# shield_I2C_latest_edit.net
KiCad netlist of a schematic drawn in Altium Designer
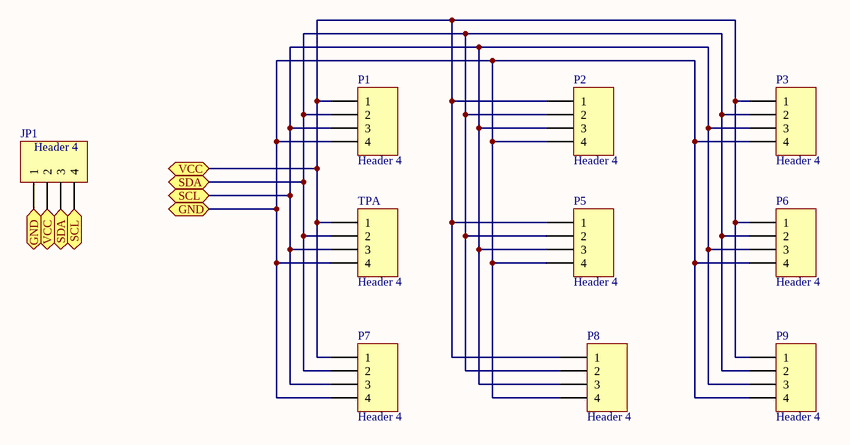
[diagram p0: shield I2C latest edit.SchDoc]

(export (version "E")
  (design (tool "Eeschema 10.0.6"))
  (components
    (comp (ref "JP1")
      (value "Header 4")
      (footprint "HDR1X4")
      (description "Header, 4-Pin")
      (fields (field (name "PUBLISHER") "Altium Limited"))
      (libsource (lib "") (part "Header 4_1"))
    )
    (comp (ref "P1")
      (value "Header 4")
      (footprint "HDR1X4")
      (description "Header, 4-Pin")
      (fields (field (name "PUBLISHER") "Altium Limited"))
      (libsource (lib "Miscellaneous Connectors") (part "Header 4"))
    )
    (comp (ref "P2")
      (value "Header 4")
      (footprint "HDR1X4")
      (description "Header, 4-Pin")
      (fields (field (name "PUBLISHER") "Altium Limited"))
      (libsource (lib "Miscellaneous Connectors") (part "Header 4"))
    )
    (comp (ref "P3")
      (value "Header 4")
      (footprint "HDR1X4")
      (description "Header, 4-Pin")
      (fields (field (name "PUBLISHER") "Altium Limited"))
      (libsource (lib "Miscellaneous Connectors") (part "Header 4"))
    )
    (comp (ref "P5")
      (value "Header 4")
      (footprint "HDR1X4")
      (description "Header, 4-Pin")
      (fields (field (name "PUBLISHER") "Altium Limited"))
      (libsource (lib "Miscellaneous Connectors") (part "Header 4"))
    )
    (comp (ref "P6")
      (value "Header 4")
      (footprint "HDR1X4")
      (description "Header, 4-Pin")
      (fields (field (name "PUBLISHER") "Altium Limited"))
      (libsource (lib "Miscellaneous Connectors") (part "Header 4"))
    )
    (comp (ref "P7")
      (value "Header 4")
      (footprint "HDR1X4")
      (description "Header, 4-Pin")
      (fields (field (name "PUBLISHER") "Altium Limited"))
      (libsource (lib "Miscellaneous Connectors") (part "Header 4"))
    )
    (comp (ref "P8")
      (value "Header 4")
      (footprint "HDR1X4")
      (description "Header, 4-Pin")
      (fields (field (name "PUBLISHER") "Altium Limited"))
      (libsource (lib "Miscellaneous Connectors") (part "Header 4"))
    )
    (comp (ref "P9")
      (value "Header 4")
      (footprint "HDR1X4")
      (description "Header, 4-Pin")
      (fields (field (name "PUBLISHER") "Altium Limited"))
      (libsource (lib "Miscellaneous Connectors") (part "Header 4"))
    )
    (comp (ref "TPA")
      (value "Header 4")
      (footprint "HDR1X4")
      (description "Header, 4-Pin")
      (fields (field (name "PUBLISHER") "Altium Limited"))
      (libsource (lib "Miscellaneous Connectors") (part "Header 4"))
    )
  )
  (nets
    (net (code "1") (name "/GND") (class "Default")
      (node (ref "JP1") (pin "1") (pinfunction "1_1") (pintype "passive"))
      (node (ref "P1") (pin "4") (pinfunction "4_4") (pintype "passive"))
      (node (ref "P2") (pin "4") (pinfunction "4_4") (pintype "passive"))
      (node (ref "P3") (pin "4") (pinfunction "4_4") (pintype "passive"))
      (node (ref "P5") (pin "4") (pinfunction "4_4") (pintype "passive"))
      (node (ref "P6") (pin "4") (pinfunction "4_4") (pintype "passive"))
      (node (ref "P7") (pin "4") (pinfunction "4_4") (pintype "passive"))
      (node (ref "P8") (pin "4") (pinfunction "4_4") (pintype "passive"))
      (node (ref "P9") (pin "4") (pinfunction "4_4") (pintype "passive"))
      (node (ref "TPA") (pin "4") (pinfunction "4_4") (pintype "passive"))
    )
    (net (code "2") (name "/SCL") (class "Default")
      (node (ref "JP1") (pin "4") (pinfunction "4_4") (pintype "passive"))
      (node (ref "P1") (pin "3") (pinfunction "3_3") (pintype "passive"))
      (node (ref "P2") (pin "3") (pinfunction "3_3") (pintype "passive"))
      (node (ref "P3") (pin "3") (pinfunction "3_3") (pintype "passive"))
      (node (ref "P5") (pin "3") (pinfunction "3_3") (pintype "passive"))
      (node (ref "P6") (pin "3") (pinfunction "3_3") (pintype "passive"))
      (node (ref "P7") (pin "3") (pinfunction "3_3") (pintype "passive"))
      (node (ref "P8") (pin "3") (pinfunction "3_3") (pintype "passive"))
      (node (ref "P9") (pin "3") (pinfunction "3_3") (pintype "passive"))
      (node (ref "TPA") (pin "3") (pinfunction "3_3") (pintype "passive"))
    )
    (net (code "3") (name "/SDA") (class "Default")
      (node (ref "JP1") (pin "3") (pinfunction "3_3") (pintype "passive"))
      (node (ref "P1") (pin "2") (pinfunction "2_2") (pintype "passive"))
      (node (ref "P2") (pin "2") (pinfunction "2_2") (pintype "passive"))
      (node (ref "P3") (pin "2") (pinfunction "2_2") (pintype "passive"))
      (node (ref "P5") (pin "2") (pinfunction "2_2") (pintype "passive"))
      (node (ref "P6") (pin "2") (pinfunction "2_2") (pintype "passive"))
      (node (ref "P7") (pin "2") (pinfunction "2_2") (pintype "passive"))
      (node (ref "P8") (pin "2") (pinfunction "2_2") (pintype "passive"))
      (node (ref "P9") (pin "2") (pinfunction "2_2") (pintype "passive"))
      (node (ref "TPA") (pin "2") (pinfunction "2_2") (pintype "passive"))
    )
    (net (code "4") (name "/VCC") (class "Default")
      (node (ref "JP1") (pin "2") (pinfunction "2_2") (pintype "passive"))
      (node (ref "P1") (pin "1") (pinfunction "1_1") (pintype "passive"))
      (node (ref "P2") (pin "1") (pinfunction "1_1") (pintype "passive"))
      (node (ref "P3") (pin "1") (pinfunction "1_1") (pintype "passive"))
      (node (ref "P5") (pin "1") (pinfunction "1_1") (pintype "passive"))
      (node (ref "P6") (pin "1") (pinfunction "1_1") (pintype "passive"))
      (node (ref "P7") (pin "1") (pinfunction "1_1") (pintype "passive"))
      (node (ref "P8") (pin "1") (pinfunction "1_1") (pintype "passive"))
      (node (ref "P9") (pin "1") (pinfunction "1_1") (pintype "passive"))
      (node (ref "TPA") (pin "1") (pinfunction "1_1") (pintype "passive"))
    )
  )
)
